# MainSheet.net
KiCad netlist of a schematic drawn in Altium Designer
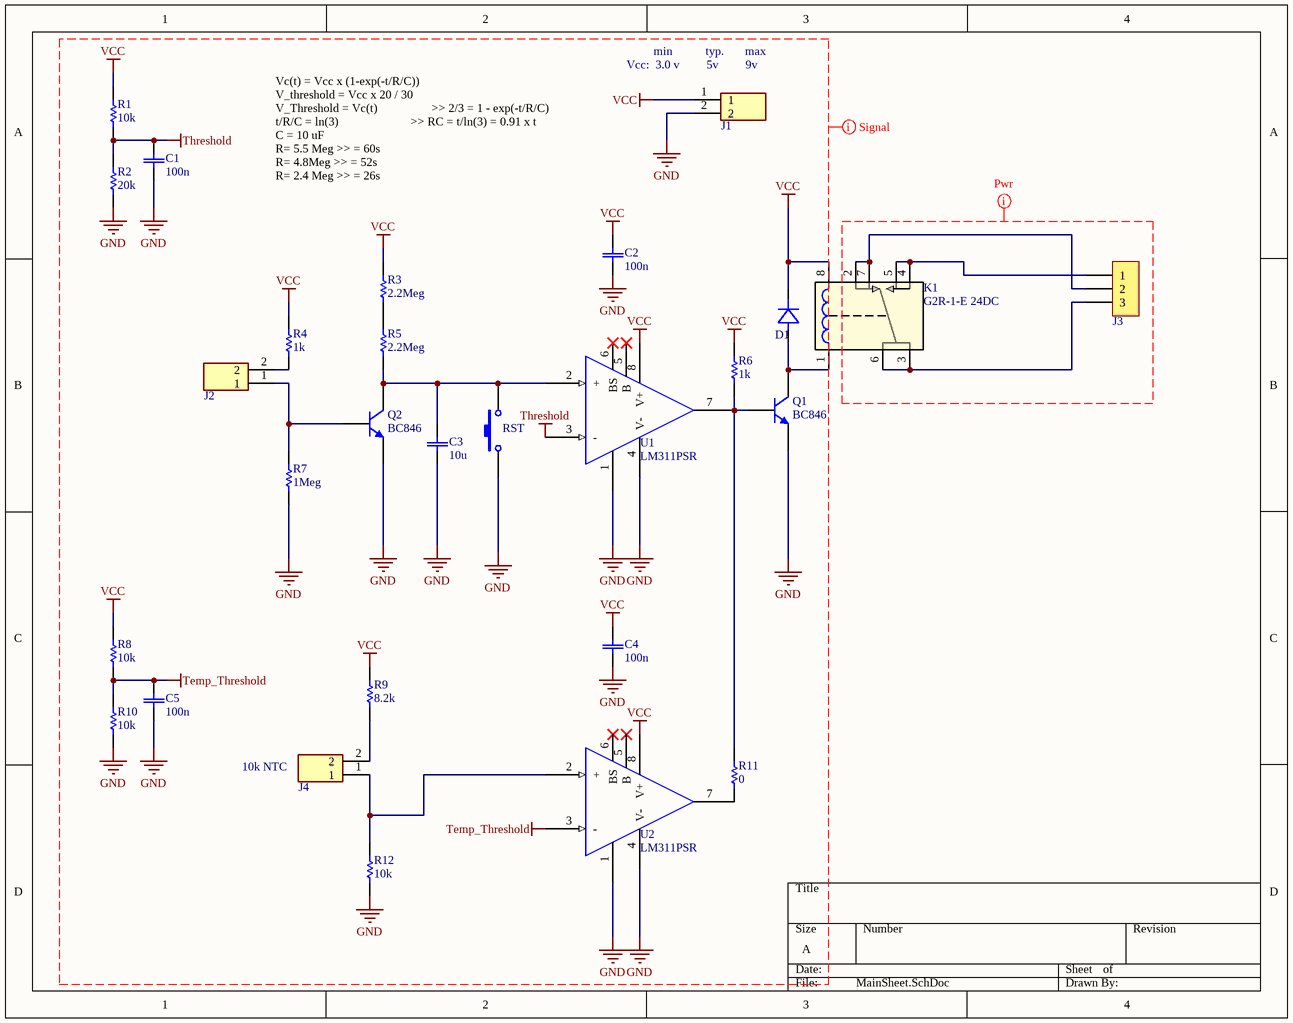
[diagram p0: MainSheet.SchDoc]

(export (version "E")
  (design (tool "Eeschema 10.0.6"))
  (components
    (comp (ref "C1")
      (value "100n")
      (footprint "CAPC180100_90N_KEM-M")
      (description "Cap, 100nF, 50v, 0603")
      (libsource (lib "CPC") (part "C0603C106M7PACTU"))
    )
    (comp (ref "C2")
      (value "100n")
      (footprint "CAPC180100_90N_KEM-M")
      (description "Cap, 100nF, 50v, 0603")
      (libsource (lib "CPC") (part "C0603C106M7PACTU"))
    )
    (comp (ref "C3")
      (value "10u")
      (footprint "CAPC180100_90N_KEM-M")
      (description "Cap 10uF, 50v, 0603")
      (libsource (lib "CPC") (part "C0603C106M7PACTU"))
    )
    (comp (ref "C4")
      (value "100n")
      (footprint "CAPC180100_90N_KEM-M")
      (description "Cap, 100nF, 50v, 0603")
      (libsource (lib "CPC") (part "C0603C106M7PACTU"))
    )
    (comp (ref "C5")
      (value "100n")
      (footprint "CAPC180100_90N_KEM-M")
      (description "Cap, 100nF, 50v, 0603")
      (libsource (lib "CPC") (part "C0603C106M7PACTU"))
    )
    (comp (ref "D1")
      (value "1N4148WSF-7")
      (footprint "SOD323F_DIO-L")
      (description "No Description Available")
      (libsource (lib "CPC") (part "1N4148WSF-7"))
    )
    (comp (ref "J1")
      (value "B2B-PH-K-S(LF)(SN)")
      (footprint "JST_B2B-PH-K-S(LF)(SN)")
      (description "Connector Header Through Hole 2 position 0.079 (2.00mm)")
      (fields (field (name "MF") "JST") (field (name "MP") "B2B-PH-K-S (LF)(SN)"))
      (libsource (lib "CPC") (part "B2B-PH-K-S(LF)(SN)"))
    )
    (comp (ref "J2")
      (value "B2B-PH-K-S(LF)(SN)")
      (footprint "JST_B2B-PH-K-S(LF)(SN)")
      (description "Connector Header Through Hole 2 position 0.079 (2.00mm)")
      (fields (field (name "MF") "JST") (field (name "MP") "B2B-PH-K-S (LF)(SN)"))
      (libsource (lib "") (part "B2B-PH-K-S(LF)(SN)_1"))
    )
    (comp (ref "J3")
      (value "2Pin Terminal")
      (footprint "KF301 2PIN")
      (description "Terminal")
      (libsource (lib "CPC") (part "3Pin Terminal"))
    )
    (comp (ref "J4")
      (value "B2B-PH-K-S(LF)(SN)")
      (footprint "JST_B2B-PH-K-S(LF)(SN)")
      (description "Connector Header Through Hole 2 position 0.079 (2.00mm)")
      (fields (field (name "MF") "JST") (field (name "MP") "B2B-PH-K-S (LF)(SN)"))
      (libsource (lib "") (part "B2B-PH-K-S(LF)(SN)_1"))
    )
    (comp (ref "K1")
      (value "G2R-1-E 24DC")
      (footprint "RELAY_G2R-1-E_OMR")
      (description "No Description Available")
      (libsource (lib "CPC") (part "G2R-1-E 24DC"))
    )
    (comp (ref "Q1")
      (value "BC846")
      (footprint "SOT23_N")
      (description "NPN General-purpose Transistor")
      (libsource (lib "CPC") (part "BC846"))
    )
    (comp (ref "Q2")
      (value "BC846")
      (footprint "SOT23_N")
      (description "NPN General-purpose Transistor")
      (libsource (lib "CPC") (part "BC846"))
    )
    (comp (ref "R1")
      (value "10k")
      (footprint "RESC3413X04N")
      (description "Res 10k, 5%,  0805")
      (libsource (lib "CPC") (part "RES 0805 0.125W"))
    )
    (comp (ref "R2")
      (value "20k")
      (footprint "RESC3413X04N")
      (description "Res 20k, 5%, 0805")
      (libsource (lib "CPC") (part "RES 0805 0.125W"))
    )
    (comp (ref "R3")
      (value "2.2Meg")
      (footprint "RESC3413X04N")
      (description "RES 0805")
      (libsource (lib "CPC") (part "RES 0805 0.125W"))
    )
    (comp (ref "R4")
      (value "1k")
      (footprint "RESC3413X04N")
      (description "RES 0805")
      (libsource (lib "CPC") (part "RES 0805 0.125W"))
    )
    (comp (ref "R5")
      (value "2.2Meg")
      (footprint "RESC3413X04N")
      (description "RES 0805")
      (libsource (lib "CPC") (part "RES 0805 0.125W"))
    )
    (comp (ref "R6")
      (value "1k")
      (footprint "RESC3413X04N")
      (description "RES 0805")
      (libsource (lib "CPC") (part "RES 0805 0.125W"))
    )
    (comp (ref "R7")
      (value "1Meg")
      (footprint "RESC3413X04N")
      (description "Res 1Meg, 5%, 0805")
      (libsource (lib "CPC") (part "RES 0805 0.125W"))
    )
    (comp (ref "R8")
      (value "10k")
      (footprint "RESC3413X04N")
      (description "Res 10k, 5%,  0805")
      (libsource (lib "CPC") (part "RES 0805 0.125W"))
    )
    (comp (ref "R9")
      (value "8.2k")
      (footprint "RESC3413X04N")
      (description "Res 8.2k, 5%,  0805")
      (libsource (lib "CPC") (part "RES 0805 0.125W"))
    )
    (comp (ref "R10")
      (value "10k")
      (footprint "RESC3413X04N")
      (description "Res 10k, 5%,  0805")
      (libsource (lib "CPC") (part "RES 0805 0.125W"))
    )
    (comp (ref "R11")
      (value "0")
      (footprint "RESC3413X04N")
      (description "RES 0805")
      (libsource (lib "CPC") (part "RES 0805 0.125W"))
    )
    (comp (ref "R12")
      (value "10k")
      (footprint "RESC3413X04N")
      (description "Res 10k, 5%,  0805")
      (libsource (lib "CPC") (part "RES 0805 0.125W"))
    )
    (comp (ref "RST")
      (value "Zero")
      (footprint "Switch - Push to On")
      (description "Push Button Switch")
      (libsource (lib "CPC") (part "Switch PB"))
    )
    (comp (ref "U1")
      (value "LM311PSR")
      (footprint "SO-8_STM-L")
      (description "No Description Available")
      (libsource (lib "CPC") (part "LM311PSR"))
    )
    (comp (ref "U2")
      (value "LM311PSR")
      (footprint "SO-8_STM-L")
      (description "No Description Available")
      (libsource (lib "CPC") (part "LM311PSR"))
    )
  )
  (nets
    (net (code "1") (name "GND") (class "Default")
      (node (ref "C1") (pin "1") (pinfunction "1_1") (pintype "passive"))
      (node (ref "C2") (pin "1") (pinfunction "1_1") (pintype "passive"))
      (node (ref "C3") (pin "1") (pinfunction "1_1") (pintype "passive"))
      (node (ref "C4") (pin "1") (pinfunction "1_1") (pintype "passive"))
      (node (ref "C5") (pin "1") (pinfunction "1_1") (pintype "passive"))
      (node (ref "J1") (pin "2") (pinfunction "2_2") (pintype "passive"))
      (node (ref "Q1") (pin "2") (pinfunction "E_2") (pintype "passive"))
      (node (ref "Q2") (pin "2") (pinfunction "E_2") (pintype "passive"))
      (node (ref "R10") (pin "1") (pinfunction "1_1") (pintype "passive"))
      (node (ref "R12") (pin "1") (pinfunction "1_1") (pintype "passive"))
      (node (ref "R2") (pin "1") (pinfunction "1_1") (pintype "passive"))
      (node (ref "R7") (pin "2") (pinfunction "2_2") (pintype "passive"))
      (node (ref "RST") (pin "1") (pinfunction "1_1") (pintype "passive"))
      (node (ref "U1") (pin "1") (pinfunction "EMITOUT_1") (pintype "power_in"))
      (node (ref "U1") (pin "4") (pinfunction "V-_4") (pintype "power_in"))
      (node (ref "U2") (pin "1") (pinfunction "EMITOUT_1") (pintype "power_in"))
      (node (ref "U2") (pin "4") (pinfunction "V-_4") (pintype "power_in"))
    )
    (net (code "2") (name "Net-(J2-Pad2)") (class "Default")
      (node (ref "J2") (pin "2") (pinfunction "2_2") (pintype "passive"))
      (node (ref "R4") (pin "1") (pinfunction "1_1") (pintype "passive"))
    )
    (net (code "3") (name "Net-(J3-Pad1)") (class "Default")
      (node (ref "J3") (pin "1") (pinfunction "1_1") (pintype "passive"))
      (node (ref "K1") (pin "4") (pinfunction "4_4") (pintype "passive"))
      (node (ref "K1") (pin "5") (pinfunction "5_5") (pintype "passive"))
    )
    (net (code "4") (name "Net-(J3-Pad2)") (class "Default")
      (node (ref "J3") (pin "2") (pinfunction "2_2") (pintype "passive"))
      (node (ref "K1") (pin "2") (pinfunction "2_2") (pintype "passive"))
      (node (ref "K1") (pin "7") (pinfunction "7_7") (pintype "passive"))
    )
    (net (code "5") (name "Net-(J3-Pad3)") (class "Default")
      (node (ref "J3") (pin "3") (pinfunction "3_3") (pintype "passive"))
      (node (ref "K1") (pin "3") (pinfunction "3_3") (pintype "passive"))
      (node (ref "K1") (pin "6") (pinfunction "6_6") (pintype "passive"))
    )
    (net (code "6") (name "Net-(J4-Pad2)") (class "Default")
      (node (ref "J4") (pin "2") (pinfunction "2_2") (pintype "passive"))
      (node (ref "R9") (pin "1") (pinfunction "1_1") (pintype "passive"))
    )
    (net (code "7") (name "Net-(Q1-B)") (class "Default")
      (node (ref "Q1") (pin "1") (pinfunction "B_1") (pintype "passive"))
      (node (ref "R11") (pin "2") (pinfunction "2_2") (pintype "passive"))
      (node (ref "R6") (pin "1") (pinfunction "1_1") (pintype "passive"))
      (node (ref "U1") (pin "7") (pinfunction "COLOUT_7") (pintype "open_collector"))
    )
    (net (code "8") (name "Net-(Q1-C)") (class "Default")
      (node (ref "D1") (pin "2") (pinfunction "2_2") (pintype "passive"))
      (node (ref "K1") (pin "1") (pinfunction "1_1") (pintype "passive"))
      (node (ref "Q1") (pin "3") (pinfunction "C_3") (pintype "passive"))
    )
    (net (code "9") (name "Net-(Q2-B)") (class "Default")
      (node (ref "J2") (pin "1") (pinfunction "1_1") (pintype "passive"))
      (node (ref "Q2") (pin "1") (pinfunction "B_1") (pintype "passive"))
      (node (ref "R7") (pin "1") (pinfunction "1_1") (pintype "passive"))
    )
    (net (code "10") (name "Net-(Q2-C)") (class "Default")
      (node (ref "C3") (pin "2") (pinfunction "2_2") (pintype "passive"))
      (node (ref "Q2") (pin "3") (pinfunction "C_3") (pintype "passive"))
      (node (ref "R5") (pin "2") (pinfunction "2_2") (pintype "passive"))
      (node (ref "RST") (pin "2") (pinfunction "2_2") (pintype "passive"))
      (node (ref "U1") (pin "2") (pinfunction "+_2") (pintype "input"))
    )
    (net (code "11") (name "Net-(R3-Pad2)") (class "Default")
      (node (ref "R3") (pin "2") (pinfunction "2_2") (pintype "passive"))
      (node (ref "R5") (pin "1") (pinfunction "1_1") (pintype "passive"))
    )
    (net (code "12") (name "Net-(U2-+)") (class "Default")
      (node (ref "J4") (pin "1") (pinfunction "1_1") (pintype "passive"))
      (node (ref "R12") (pin "2") (pinfunction "2_2") (pintype "passive"))
      (node (ref "U2") (pin "2") (pinfunction "+_2") (pintype "input"))
    )
    (net (code "13") (name "Net-(U2-COLOUT)") (class "Default")
      (node (ref "R11") (pin "1") (pinfunction "1_1") (pintype "passive"))
      (node (ref "U2") (pin "7") (pinfunction "COLOUT_7") (pintype "open_collector"))
    )
    (net (code "14") (name "Temp_Threshold") (class "Default")
      (node (ref "C5") (pin "2") (pinfunction "2_2") (pintype "passive"))
      (node (ref "R10") (pin "2") (pinfunction "2_2") (pintype "passive"))
      (node (ref "R8") (pin "1") (pinfunction "1_1") (pintype "passive"))
      (node (ref "U2") (pin "3") (pinfunction "-_3") (pintype "input"))
    )
    (net (code "15") (name "Threshold") (class "Default")
      (node (ref "C1") (pin "2") (pinfunction "2_2") (pintype "passive"))
      (node (ref "R1") (pin "1") (pinfunction "1_1") (pintype "passive"))
      (node (ref "R2") (pin "2") (pinfunction "2_2") (pintype "passive"))
      (node (ref "U1") (pin "3") (pinfunction "-_3") (pintype "input"))
    )
    (net (code "16") (name "VCC") (class "Default")
      (node (ref "C2") (pin "2") (pinfunction "2_2") (pintype "passive"))
      (node (ref "C4") (pin "2") (pinfunction "2_2") (pintype "passive"))
      (node (ref "D1") (pin "1") (pinfunction "1_1") (pintype "passive"))
      (node (ref "J1") (pin "1") (pinfunction "1_1") (pintype "passive"))
      (node (ref "K1") (pin "8") (pinfunction "8_8") (pintype "passive"))
      (node (ref "R1") (pin "2") (pinfunction "2_2") (pintype "passive"))
      (node (ref "R3") (pin "1") (pinfunction "1_1") (pintype "passive"))
      (node (ref "R4") (pin "2") (pinfunction "2_2") (pintype "passive"))
      (node (ref "R6") (pin "2") (pinfunction "2_2") (pintype "passive"))
      (node (ref "R8") (pin "2") (pinfunction "2_2") (pintype "passive"))
      (node (ref "R9") (pin "2") (pinfunction "2_2") (pintype "passive"))
      (node (ref "U1") (pin "8") (pinfunction "V+_8") (pintype "power_in"))
      (node (ref "U2") (pin "8") (pinfunction "V+_8") (pintype "power_in"))
    )
    (net (code "17") (name "unconnected-(U1-B-Pad5)") (class "Default")
      (node (ref "U1") (pin "5") (pinfunction "B_5") (pintype "passive+no_connect"))
    )
    (net (code "18") (name "unconnected-(U1-BS-Pad6)") (class "Default")
      (node (ref "U1") (pin "6") (pinfunction "BS_6") (pintype "passive+no_connect"))
    )
    (net (code "19") (name "unconnected-(U2-B-Pad5)") (class "Default")
      (node (ref "U2") (pin "5") (pinfunction "B_5") (pintype "passive+no_connect"))
    )
    (net (code "20") (name "unconnected-(U2-BS-Pad6)") (class "Default")
      (node (ref "U2") (pin "6") (pinfunction "BS_6") (pintype "passive+no_connect"))
    )
  )
)
